# SP8T_ecal_1.net
KiCad netlist of a schematic drawn in Altium Designer
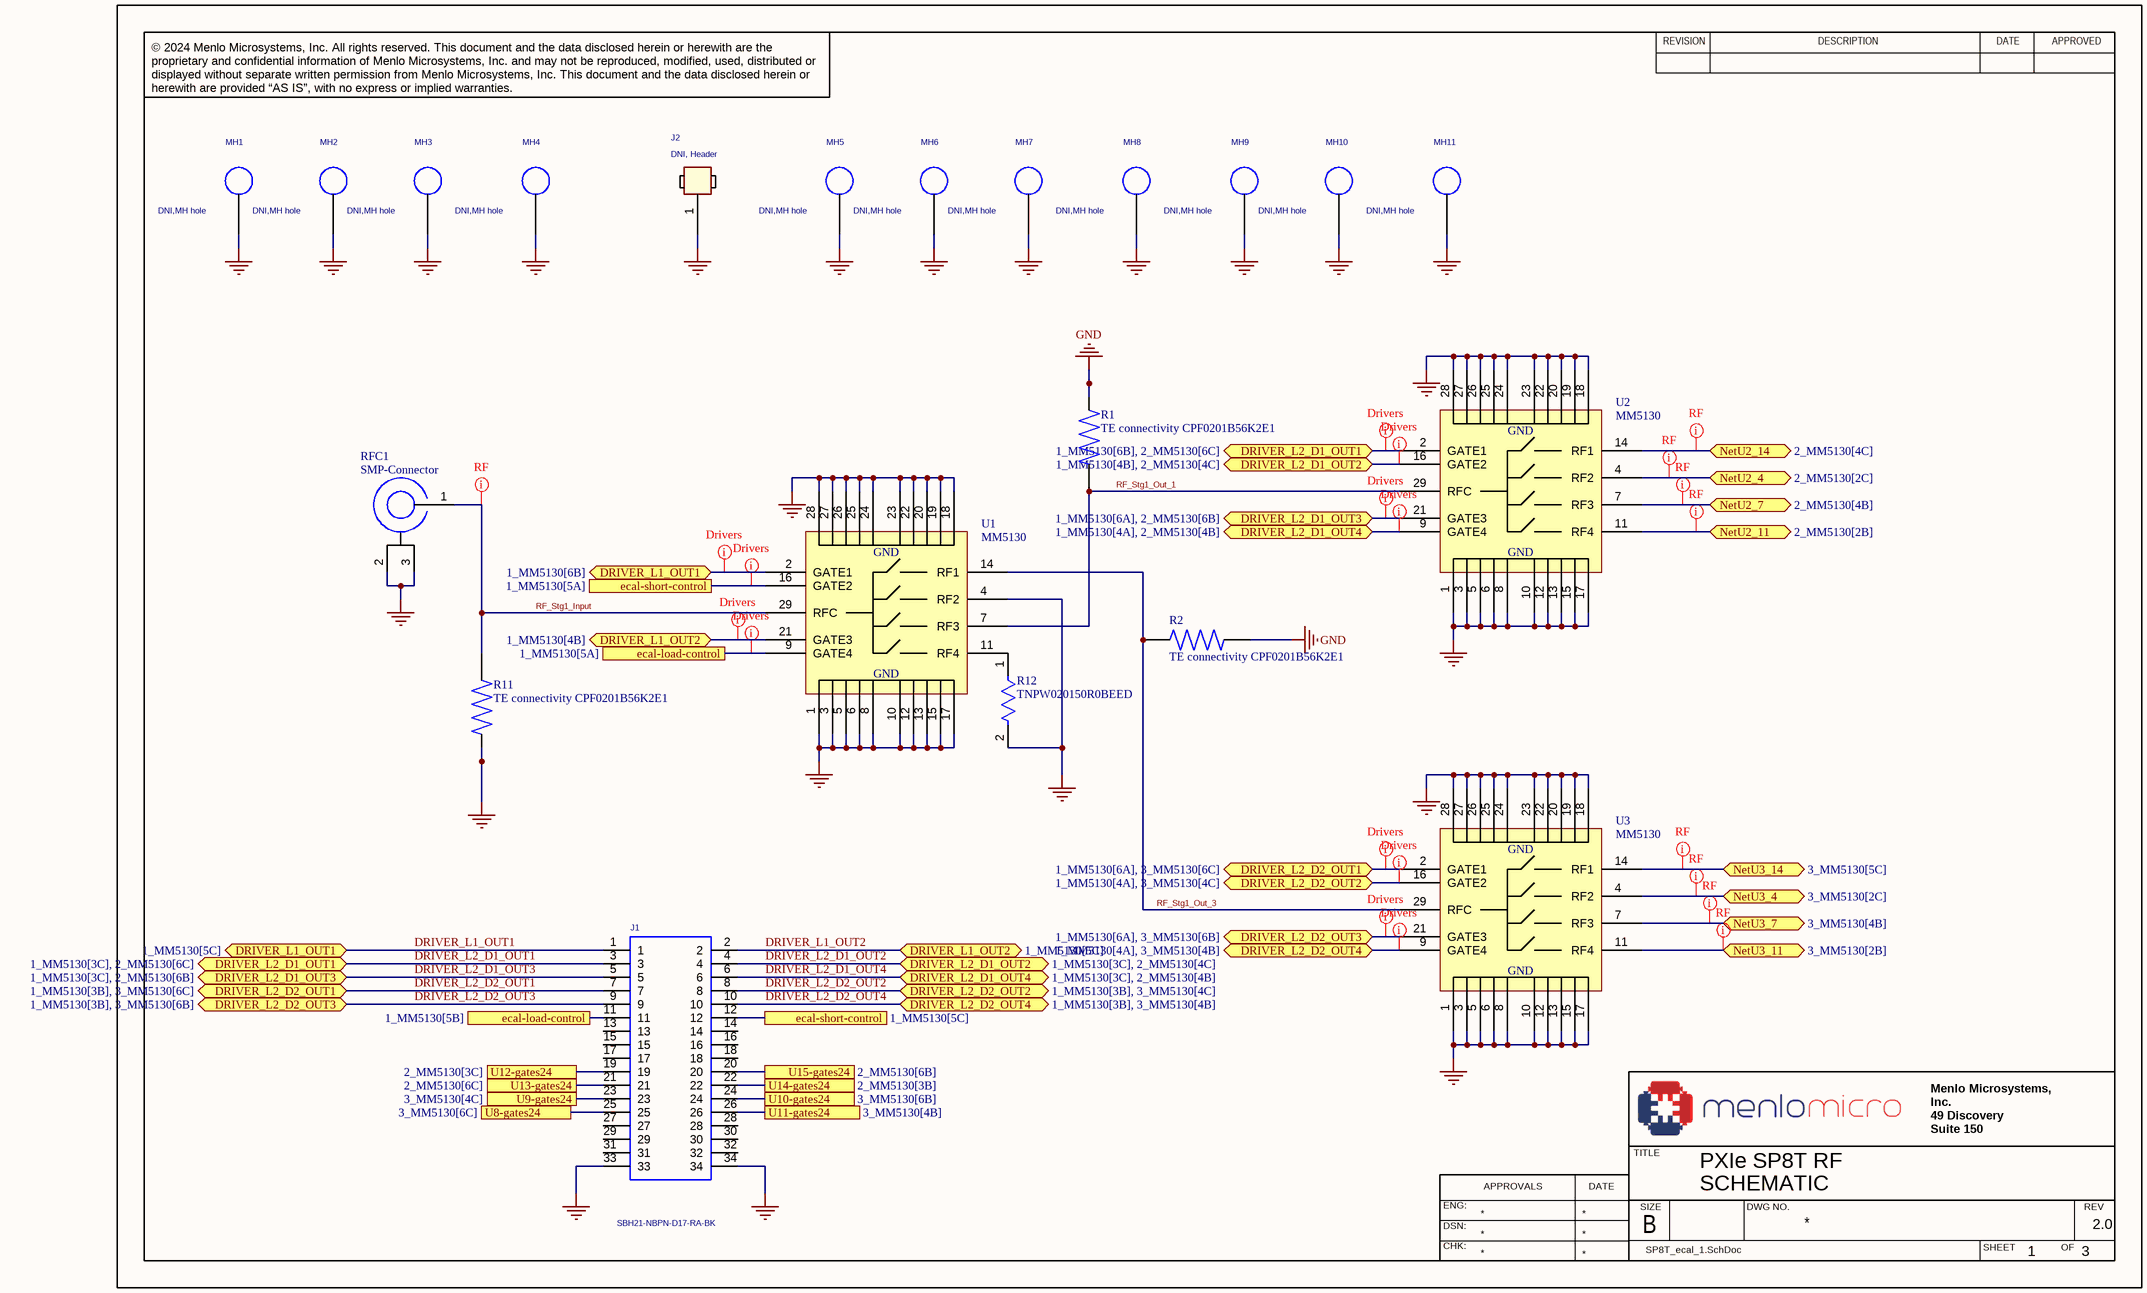
[diagram p0: SP8T_ecal_1.SchDoc]

(export (version "E")
  (design (tool "Eeschema 10.0.6"))
  (components
    (comp (ref "J1")
      (value "SBH21-NBPN-D17-RA-BK")
      (footprint "SULLINS_SBH21-NBPN-D17-ST-B")
      (description "Connector Header Through Hole 34 position 0.079 _2.00mm_")
      (libsource (lib "*") (part "SBH21-NBPN-D17-ST-BK"))
    )
    (comp (ref "J2") (value "DNI, Header") (footprint "tp_0035") (libsource (lib "*") (part "HEADER 1")))
    (comp (ref "MH1") (value "DNI,MH hole") (footprint "MH") (libsource (lib "*") (part "M HOLE1_0")))
    (comp (ref "MH2") (value "DNI,MH hole") (footprint "MH") (libsource (lib "*") (part "M HOLE1_0")))
    (comp (ref "MH3") (value "DNI,MH hole") (footprint "MH") (libsource (lib "*") (part "M HOLE1_0")))
    (comp (ref "MH4") (value "DNI,MH hole") (footprint "MH") (libsource (lib "*") (part "M HOLE1_0")))
    (comp (ref "MH5") (value "DNI,MH hole") (footprint "MH_55") (libsource (lib "*") (part "M HOLE1_0")))
    (comp (ref "MH6") (value "DNI,MH hole") (footprint "MH_55") (libsource (lib "*") (part "M HOLE1_0")))
    (comp (ref "MH7") (value "DNI,MH hole") (footprint "MH_55") (libsource (lib "*") (part "M HOLE1_0")))
    (comp (ref "MH8") (value "DNI,MH hole") (footprint "MH_55") (libsource (lib "*") (part "M HOLE1_0")))
    (comp (ref "MH9") (value "DNI,MH hole") (footprint "MH_55") (libsource (lib "*") (part "M HOLE1_0")))
    (comp (ref "MH10") (value "DNI,MH hole") (footprint "MH_55") (libsource (lib "*") (part "M HOLE1_0")))
    (comp (ref "MH11") (value "DNI,MH hole") (footprint "MH_55") (libsource (lib "*") (part "M HOLE1_0")))
    (comp (ref "R1")
      (value "TE connectivity CPF0201B56K2E1")
      (footprint "0201-resistor")
      (description "CPF 0201 56K2 0.1% 25PPM 1K RL")
      (fields (field (name "MP") "ERJ1GN0R00C") (field (name "MFGR PART NO.") "CPF0201B56K2E1"))
      (libsource (lib "SchlibLafe") (part "TE connectivity CPF0201B56K2E1"))
    )
    (comp (ref "R2")
      (value "TE connectivity CPF0201B56K2E1")
      (footprint "0201-resistor")
      (description "CPF 0201 56K2 0.1% 25PPM 1K RL")
      (fields (field (name "MP") "ERJ1GN0R00C") (field (name "MFGR PART NO.") "CPF0201B56K2E1"))
      (libsource (lib "SchlibLafe") (part "TE connectivity CPF0201B56K2E1"))
    )
    (comp (ref "R11")
      (value "TE connectivity CPF0201B56K2E1")
      (footprint "0201-resistor")
      (description "CPF 0201 56K2 0.1% 25PPM 1K RL")
      (fields (field (name "MP") "ERJ1GN0R00C") (field (name "MFGR PART NO.") "CPF0201B56K2E1"))
      (libsource (lib "SchlibLafe") (part "TE connectivity CPF0201B56K2E1"))
    )
    (comp (ref "R12")
      (value "TNPW020150R0BEED")
      (footprint "FP-ERJ1GN-IPC_C")
      (description "RES SMD 50 OHM 0.1% 1/20W 0201")
      (fields (field (name "TOLERANCE") "1%"))
      (libsource (lib "Altium Content Vault") (part "1029c3af85768c4190bb7ad29bc67b5"))
    )
    (comp (ref "RFC1")
      (value "PE44490")
      (footprint "CONN-PE44490")
      (description "SMP, Mini Connector Plug, Male Pin 50 Ohms Board Edge, Cutout; Surface Mount Solder")
      (fields (field (name "MANUFACTURER") "Pasternack") (field (name "TYPE") "SMP-Connector"))
      (libsource (lib "Menlo_Altium_Library") (part "CONN-PE44490"))
    )
    (comp (ref "U1")
      (value "MM5130")
      (footprint "MM5130-NORM_PCB_NOFLOOD")
      (description "High power SP4T MEMs switch")
      (libsource (lib "Menlo_Altium_Library") (part "IC-MM5130"))
    )
    (comp (ref "U2")
      (value "MM5130")
      (footprint "MM5130-NORM_PCB_NOFLOOD")
      (description "High power SP4T MEMs switch")
      (libsource (lib "Menlo_Altium_Library") (part "IC-MM5130"))
    )
    (comp (ref "U3")
      (value "MM5130")
      (footprint "MM5130-NORM_PCB_NOFLOOD")
      (description "High power SP4T MEMs switch")
      (libsource (lib "Menlo_Altium_Library") (part "IC-MM5130"))
    )
  )
  (nets
    (net (code "1") (name "/DRIVER_L1_OUT1") (class "Default")
      (node (ref "J1") (pin "1") (pinfunction "1_1") (pintype "passive"))
      (node (ref "U1") (pin "2") (pinfunction "GATE1_2") (pintype "passive"))
    )
    (net (code "2") (name "/DRIVER_L1_OUT2") (class "Default")
      (node (ref "J1") (pin "2") (pinfunction "2_2") (pintype "passive"))
      (node (ref "U1") (pin "21") (pinfunction "GATE3_21") (pintype "passive"))
    )
    (net (code "3") (name "/DRIVER_L2_D1_OUT1") (class "Default")
      (node (ref "J1") (pin "3") (pinfunction "3_3") (pintype "passive"))
      (node (ref "U2") (pin "2") (pinfunction "GATE1_2") (pintype "passive"))
    )
    (net (code "4") (name "/DRIVER_L2_D1_OUT2") (class "Default")
      (node (ref "J1") (pin "4") (pinfunction "4_4") (pintype "passive"))
      (node (ref "U2") (pin "16") (pinfunction "GATE2_16") (pintype "passive"))
    )
    (net (code "5") (name "/DRIVER_L2_D1_OUT3") (class "Default")
      (node (ref "J1") (pin "5") (pinfunction "5_5") (pintype "passive"))
      (node (ref "U2") (pin "21") (pinfunction "GATE3_21") (pintype "passive"))
    )
    (net (code "6") (name "/DRIVER_L2_D1_OUT4") (class "Default")
      (node (ref "J1") (pin "6") (pinfunction "6_6") (pintype "passive"))
      (node (ref "U2") (pin "9") (pinfunction "GATE4_9") (pintype "passive"))
    )
    (net (code "7") (name "/DRIVER_L2_D2_OUT1") (class "Default")
      (node (ref "J1") (pin "7") (pinfunction "7_7") (pintype "passive"))
      (node (ref "U3") (pin "2") (pinfunction "GATE1_2") (pintype "passive"))
    )
    (net (code "8") (name "/DRIVER_L2_D2_OUT2") (class "Default")
      (node (ref "J1") (pin "8") (pinfunction "8_8") (pintype "passive"))
      (node (ref "U3") (pin "16") (pinfunction "GATE2_16") (pintype "passive"))
    )
    (net (code "9") (name "/DRIVER_L2_D2_OUT3") (class "Default")
      (node (ref "J1") (pin "9") (pinfunction "9_9") (pintype "passive"))
      (node (ref "U3") (pin "21") (pinfunction "GATE3_21") (pintype "passive"))
    )
    (net (code "10") (name "/DRIVER_L2_D2_OUT4") (class "Default")
      (node (ref "J1") (pin "10") (pinfunction "10_10") (pintype "passive"))
      (node (ref "U3") (pin "9") (pinfunction "GATE4_9") (pintype "passive"))
    )
    (net (code "11") (name "/NetU2_4") (class "Default")
      (node (ref "U2") (pin "4") (pinfunction "RF2_4") (pintype "passive"))
    )
    (net (code "12") (name "/NetU2_7") (class "Default")
      (node (ref "U2") (pin "7") (pinfunction "RF3_7") (pintype "passive"))
    )
    (net (code "13") (name "/NetU2_11") (class "Default")
      (node (ref "U2") (pin "11") (pinfunction "RF4_11") (pintype "passive"))
    )
    (net (code "14") (name "/NetU2_14") (class "Default")
      (node (ref "U2") (pin "14") (pinfunction "RF1_14") (pintype "passive"))
    )
    (net (code "15") (name "/NetU3_4") (class "Default")
      (node (ref "U3") (pin "4") (pinfunction "RF2_4") (pintype "passive"))
    )
    (net (code "16") (name "/NetU3_7") (class "Default")
      (node (ref "U3") (pin "7") (pinfunction "RF3_7") (pintype "passive"))
    )
    (net (code "17") (name "/NetU3_11") (class "Default")
      (node (ref "U3") (pin "11") (pinfunction "RF4_11") (pintype "passive"))
    )
    (net (code "18") (name "/NetU3_14") (class "Default")
      (node (ref "U3") (pin "14") (pinfunction "RF1_14") (pintype "passive"))
    )
    (net (code "19") (name "/RF_Stg1_Input") (class "Default")
      (node (ref "R11") (pin "1") (pinfunction "1_1") (pintype "passive"))
      (node (ref "RFC1") (pin "1") (pinfunction "1_1") (pintype "passive"))
      (node (ref "U1") (pin "29") (pinfunction "RFC_29") (pintype "passive"))
    )
    (net (code "20") (name "/RF_Stg1_Out_1") (class "Default")
      (node (ref "R1") (pin "1") (pinfunction "1_1") (pintype "passive"))
      (node (ref "U1") (pin "7") (pinfunction "RF3_7") (pintype "passive"))
      (node (ref "U2") (pin "29") (pinfunction "RFC_29") (pintype "passive"))
    )
    (net (code "21") (name "/RF_Stg1_Out_3") (class "Default")
      (node (ref "R2") (pin "2") (pinfunction "2_2") (pintype "passive"))
      (node (ref "U1") (pin "14") (pinfunction "RF1_14") (pintype "passive"))
      (node (ref "U3") (pin "29") (pinfunction "RFC_29") (pintype "passive"))
    )
    (net (code "22") (name "/U8-gates24") (class "Default")
      (node (ref "J1") (pin "25") (pinfunction "25_25") (pintype "passive"))
    )
    (net (code "23") (name "/U9-gates24") (class "Default")
      (node (ref "J1") (pin "23") (pinfunction "23_23") (pintype "passive"))
    )
    (net (code "24") (name "/U10-gates24") (class "Default")
      (node (ref "J1") (pin "24") (pinfunction "24_24") (pintype "passive"))
    )
    (net (code "25") (name "/U11-gates24") (class "Default")
      (node (ref "J1") (pin "26") (pinfunction "26_26") (pintype "passive"))
    )
    (net (code "26") (name "/U12-gates24") (class "Default")
      (node (ref "J1") (pin "19") (pinfunction "19_19") (pintype "passive"))
    )
    (net (code "27") (name "/U13-gates24") (class "Default")
      (node (ref "J1") (pin "21") (pinfunction "21_21") (pintype "passive"))
    )
    (net (code "28") (name "/U14-gates24") (class "Default")
      (node (ref "J1") (pin "22") (pinfunction "22_22") (pintype "passive"))
    )
    (net (code "29") (name "/U15-gates24") (class "Default")
      (node (ref "J1") (pin "20") (pinfunction "20_20") (pintype "passive"))
    )
    (net (code "30") (name "/ecal-load-control") (class "Default")
      (node (ref "J1") (pin "11") (pinfunction "11_11") (pintype "passive"))
      (node (ref "U1") (pin "9") (pinfunction "GATE4_9") (pintype "passive"))
    )
    (net (code "31") (name "/ecal-short-control") (class "Default")
      (node (ref "J1") (pin "12") (pinfunction "12_12") (pintype "passive"))
      (node (ref "U1") (pin "16") (pinfunction "GATE2_16") (pintype "passive"))
    )
    (net (code "32") (name "GND") (class "Default")
      (node (ref "J1") (pin "33") (pinfunction "33_33") (pintype "passive"))
      (node (ref "J1") (pin "34") (pinfunction "34_34") (pintype "passive"))
      (node (ref "J2") (pin "1") (pinfunction "1_1") (pintype "passive"))
      (node (ref "MH1") (pin "1") (pinfunction "1_1") (pintype "passive"))
      (node (ref "MH10") (pin "1") (pinfunction "1_1") (pintype "passive"))
      (node (ref "MH11") (pin "1") (pinfunction "1_1") (pintype "passive"))
      (node (ref "MH2") (pin "1") (pinfunction "1_1") (pintype "passive"))
      (node (ref "MH3") (pin "1") (pinfunction "1_1") (pintype "passive"))
      (node (ref "MH4") (pin "1") (pinfunction "1_1") (pintype "passive"))
      (node (ref "MH5") (pin "1") (pinfunction "1_1") (pintype "passive"))
      (node (ref "MH6") (pin "1") (pinfunction "1_1") (pintype "passive"))
      (node (ref "MH7") (pin "1") (pinfunction "1_1") (pintype "passive"))
      (node (ref "MH8") (pin "1") (pinfunction "1_1") (pintype "passive"))
      (node (ref "MH9") (pin "1") (pinfunction "1_1") (pintype "passive"))
      (node (ref "R1") (pin "2") (pinfunction "2_2") (pintype "passive"))
      (node (ref "R11") (pin "2") (pinfunction "2_2") (pintype "passive"))
      (node (ref "R12") (pin "2") (pinfunction "2_2") (pintype "passive"))
      (node (ref "R2") (pin "1") (pinfunction "1_1") (pintype "passive"))
      (node (ref "RFC1") (pin "2") (pinfunction "2_2") (pintype "passive"))
      (node (ref "RFC1") (pin "3") (pinfunction "3_3") (pintype "passive"))
      (node (ref "U1") (pin "1") (pinfunction "GND_1") (pintype "passive"))
      (node (ref "U1") (pin "10") (pinfunction "GND_10") (pintype "passive"))
      (node (ref "U1") (pin "12") (pinfunction "GND_12") (pintype "passive"))
      (node (ref "U1") (pin "13") (pinfunction "GND_13") (pintype "passive"))
      (node (ref "U1") (pin "15") (pinfunction "GND_15") (pintype "passive"))
      (node (ref "U1") (pin "17") (pinfunction "GND_17") (pintype "passive"))
      (node (ref "U1") (pin "18") (pinfunction "GND_18") (pintype "passive"))
      (node (ref "U1") (pin "19") (pinfunction "GND_19") (pintype "passive"))
      (node (ref "U1") (pin "20") (pinfunction "GND_20") (pintype "passive"))
      (node (ref "U1") (pin "22") (pinfunction "GND_22") (pintype "passive"))
      (node (ref "U1") (pin "23") (pinfunction "GND_23") (pintype "passive"))
      (node (ref "U1") (pin "24") (pinfunction "GND_24") (pintype "passive"))
      (node (ref "U1") (pin "25") (pinfunction "GND_25") (pintype "passive"))
      (node (ref "U1") (pin "26") (pinfunction "GND_26") (pintype "passive"))
      (node (ref "U1") (pin "27") (pinfunction "GND_27") (pintype "passive"))
      (node (ref "U1") (pin "28") (pinfunction "GND_28") (pintype "passive"))
      (node (ref "U1") (pin "3") (pinfunction "GND_3") (pintype "passive"))
      (node (ref "U1") (pin "4") (pinfunction "RF2_4") (pintype "passive"))
      (node (ref "U1") (pin "5") (pinfunction "GND_5") (pintype "passive"))
      (node (ref "U1") (pin "6") (pinfunction "GND_6") (pintype "passive"))
      (node (ref "U1") (pin "8") (pinfunction "GND_8") (pintype "passive"))
      (node (ref "U2") (pin "1") (pinfunction "GND_1") (pintype "passive"))
      (node (ref "U2") (pin "10") (pinfunction "GND_10") (pintype "passive"))
      (node (ref "U2") (pin "12") (pinfunction "GND_12") (pintype "passive"))
      (node (ref "U2") (pin "13") (pinfunction "GND_13") (pintype "passive"))
      (node (ref "U2") (pin "15") (pinfunction "GND_15") (pintype "passive"))
      (node (ref "U2") (pin "17") (pinfunction "GND_17") (pintype "passive"))
      (node (ref "U2") (pin "18") (pinfunction "GND_18") (pintype "passive"))
      (node (ref "U2") (pin "19") (pinfunction "GND_19") (pintype "passive"))
      (node (ref "U2") (pin "20") (pinfunction "GND_20") (pintype "passive"))
      (node (ref "U2") (pin "22") (pinfunction "GND_22") (pintype "passive"))
      (node (ref "U2") (pin "23") (pinfunction "GND_23") (pintype "passive"))
      (node (ref "U2") (pin "24") (pinfunction "GND_24") (pintype "passive"))
      (node (ref "U2") (pin "25") (pinfunction "GND_25") (pintype "passive"))
      (node (ref "U2") (pin "26") (pinfunction "GND_26") (pintype "passive"))
      (node (ref "U2") (pin "27") (pinfunction "GND_27") (pintype "passive"))
      (node (ref "U2") (pin "28") (pinfunction "GND_28") (pintype "passive"))
      (node (ref "U2") (pin "3") (pinfunction "GND_3") (pintype "passive"))
      (node (ref "U2") (pin "5") (pinfunction "GND_5") (pintype "passive"))
      (node (ref "U2") (pin "6") (pinfunction "GND_6") (pintype "passive"))
      (node (ref "U2") (pin "8") (pinfunction "GND_8") (pintype "passive"))
      (node (ref "U3") (pin "1") (pinfunction "GND_1") (pintype "passive"))
      (node (ref "U3") (pin "10") (pinfunction "GND_10") (pintype "passive"))
      (node (ref "U3") (pin "12") (pinfunction "GND_12") (pintype "passive"))
      (node (ref "U3") (pin "13") (pinfunction "GND_13") (pintype "passive"))
      (node (ref "U3") (pin "15") (pinfunction "GND_15") (pintype "passive"))
      (node (ref "U3") (pin "17") (pinfunction "GND_17") (pintype "passive"))
      (node (ref "U3") (pin "18") (pinfunction "GND_18") (pintype "passive"))
      (node (ref "U3") (pin "19") (pinfunction "GND_19") (pintype "passive"))
      (node (ref "U3") (pin "20") (pinfunction "GND_20") (pintype "passive"))
      (node (ref "U3") (pin "22") (pinfunction "GND_22") (pintype "passive"))
      (node (ref "U3") (pin "23") (pinfunction "GND_23") (pintype "passive"))
      (node (ref "U3") (pin "24") (pinfunction "GND_24") (pintype "passive"))
      (node (ref "U3") (pin "25") (pinfunction "GND_25") (pintype "passive"))
      (node (ref "U3") (pin "26") (pinfunction "GND_26") (pintype "passive"))
      (node (ref "U3") (pin "27") (pinfunction "GND_27") (pintype "passive"))
      (node (ref "U3") (pin "28") (pinfunction "GND_28") (pintype "passive"))
      (node (ref "U3") (pin "3") (pinfunction "GND_3") (pintype "passive"))
      (node (ref "U3") (pin "5") (pinfunction "GND_5") (pintype "passive"))
      (node (ref "U3") (pin "6") (pinfunction "GND_6") (pintype "passive"))
      (node (ref "U3") (pin "8") (pinfunction "GND_8") (pintype "passive"))
    )
    (net (code "33") (name "Net-(U1-RF4)") (class "Default")
      (node (ref "R12") (pin "1") (pinfunction "1_1") (pintype "passive"))
      (node (ref "U1") (pin "11") (pinfunction "RF4_11") (pintype "passive"))
    )
    (net (code "34") (name "unconnected-(J1-Pad13)") (class "Default")
      (node (ref "J1") (pin "13") (pinfunction "13_13") (pintype "passive"))
    )
    (net (code "35") (name "unconnected-(J1-Pad14)") (class "Default")
      (node (ref "J1") (pin "14") (pinfunction "14_14") (pintype "passive"))
    )
    (net (code "36") (name "unconnected-(J1-Pad15)") (class "Default")
      (node (ref "J1") (pin "15") (pinfunction "15_15") (pintype "passive"))
    )
    (net (code "37") (name "unconnected-(J1-Pad16)") (class "Default")
      (node (ref "J1") (pin "16") (pinfunction "16_16") (pintype "passive"))
    )
    (net (code "38") (name "unconnected-(J1-Pad17)") (class "Default")
      (node (ref "J1") (pin "17") (pinfunction "17_17") (pintype "passive"))
    )
    (net (code "39") (name "unconnected-(J1-Pad18)") (class "Default")
      (node (ref "J1") (pin "18") (pinfunction "18_18") (pintype "passive"))
    )
    (net (code "40") (name "unconnected-(J1-Pad27)") (class "Default")
      (node (ref "J1") (pin "27") (pinfunction "27_27") (pintype "passive"))
    )
    (net (code "41") (name "unconnected-(J1-Pad28)") (class "Default")
      (node (ref "J1") (pin "28") (pinfunction "28_28") (pintype "passive"))
    )
    (net (code "42") (name "unconnected-(J1-Pad29)") (class "Default")
      (node (ref "J1") (pin "29") (pinfunction "29_29") (pintype "passive"))
    )
    (net (code "43") (name "unconnected-(J1-Pad30)") (class "Default")
      (node (ref "J1") (pin "30") (pinfunction "30_30") (pintype "passive"))
    )
    (net (code "44") (name "unconnected-(J1-Pad31)") (class "Default")
      (node (ref "J1") (pin "31") (pinfunction "31_31") (pintype "passive"))
    )
    (net (code "45") (name "unconnected-(J1-Pad32)") (class "Default")
      (node (ref "J1") (pin "32") (pinfunction "32_32") (pintype "passive"))
    )
  )
)
